# Sheet1.net
KiCad netlist of a schematic drawn in Altium Designer
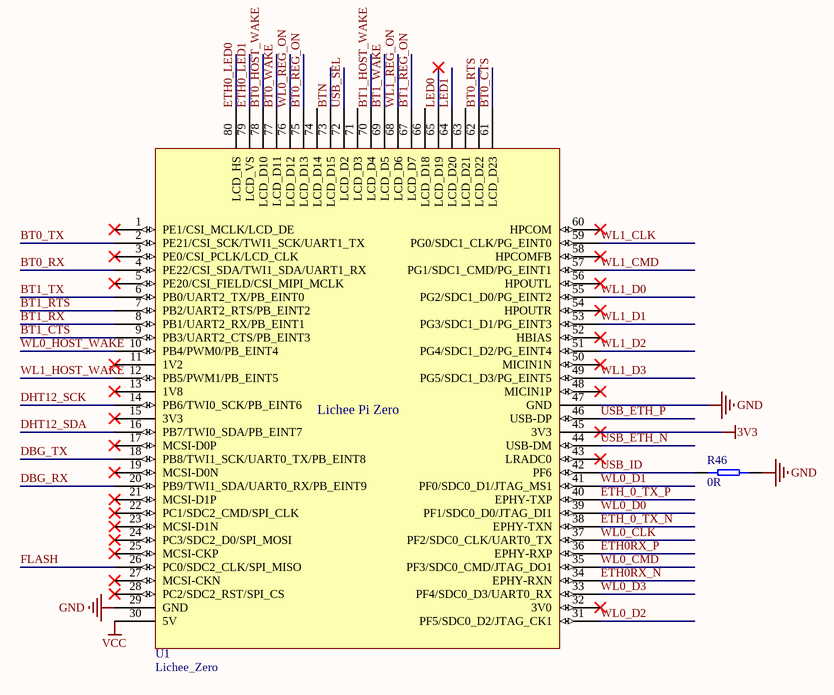
[diagram p0: Sheet1.SchDoc]

(export (version "E")
  (design (tool "Eeschema 10.0.6"))
  (components
    (comp (ref "R46") (value "0R") (footprint "0805R") (libsource (lib "Zero") (part "R")))
    (comp (ref "U1")
      (value "Lichee_Zero")
      (footprint "Lichee_Zero_Full")
      (description "Lichee_pizero LPZ1011")
      (libsource (lib "CTC") (part "Lichee_Zero_Full"))
    )
  )
  (nets
    (net (code "1") (name "/BT0_CTS") (class "Default")
      (node (ref "U1") (pin "61") (pinfunction "LCD_D23_61") (pintype "passive"))
    )
    (net (code "2") (name "/BT0_HOST_WAKE") (class "Default")
      (node (ref "U1") (pin "78") (pinfunction "LCD_D10_78") (pintype "passive"))
    )
    (net (code "3") (name "/BT0_REG_ON") (class "Default")
      (node (ref "U1") (pin "75") (pinfunction "LCD_D13_75") (pintype "passive"))
    )
    (net (code "4") (name "/BT0_RTS") (class "Default")
      (node (ref "U1") (pin "62") (pinfunction "LCD_D22_62") (pintype "passive"))
    )
    (net (code "5") (name "/BT0_RX") (class "Default")
      (node (ref "U1") (pin "4") (pinfunction "PE22/CSI_SDA/TWI1_SDA/UART1_RX_4") (pintype "bidirectional"))
    )
    (net (code "6") (name "/BT0_TX") (class "Default")
      (node (ref "U1") (pin "2") (pinfunction "PE21/CSI_SCK/TWI1_SCK/UART1_TX_2") (pintype "bidirectional"))
    )
    (net (code "7") (name "/BT0_WAKE") (class "Default")
      (node (ref "U1") (pin "77") (pinfunction "LCD_D11_77") (pintype "passive"))
    )
    (net (code "8") (name "/BT1_CTS") (class "Default")
      (node (ref "U1") (pin "9") (pinfunction "PB3/UART2_CTS/PB_EINT3_9") (pintype "bidirectional"))
    )
    (net (code "9") (name "/BT1_HOST_WAKE") (class "Default")
      (node (ref "U1") (pin "70") (pinfunction "LCD_D4_70") (pintype "passive"))
    )
    (net (code "10") (name "/BT1_REG_ON") (class "Default")
      (node (ref "U1") (pin "67") (pinfunction "LCD_D7_67") (pintype "passive"))
    )
    (net (code "11") (name "/BT1_RTS") (class "Default")
      (node (ref "U1") (pin "7") (pinfunction "PB2/UART2_RTS/PB_EINT2_7") (pintype "bidirectional"))
    )
    (net (code "12") (name "/BT1_RX") (class "Default")
      (node (ref "U1") (pin "8") (pinfunction "PB1/UART2_RX/PB_EINT1_8") (pintype "bidirectional"))
    )
    (net (code "13") (name "/BT1_TX") (class "Default")
      (node (ref "U1") (pin "6") (pinfunction "PB0/UART2_TX/PB_EINT0_6") (pintype "bidirectional"))
    )
    (net (code "14") (name "/BT1_WAKE") (class "Default")
      (node (ref "U1") (pin "69") (pinfunction "LCD_D5_69") (pintype "passive"))
    )
    (net (code "15") (name "/BTN") (class "Default")
      (node (ref "U1") (pin "73") (pinfunction "LCD_D15_73") (pintype "passive"))
    )
    (net (code "16") (name "/DBG_RX") (class "Default")
      (node (ref "U1") (pin "20") (pinfunction "PB9/TWI1_SDA/UART0_RX/PB_EINT9_20") (pintype "bidirectional"))
    )
    (net (code "17") (name "/DBG_TX") (class "Default")
      (node (ref "U1") (pin "18") (pinfunction "PB8/TWI1_SCK/UART0_TX/PB_EINT8_18") (pintype "bidirectional"))
    )
    (net (code "18") (name "/DHT12_SCK") (class "Default")
      (node (ref "U1") (pin "14") (pinfunction "PB6/TWI0_SCK/PB_EINT6_14") (pintype "bidirectional"))
    )
    (net (code "19") (name "/DHT12_SDA") (class "Default")
      (node (ref "U1") (pin "16") (pinfunction "PB7/TWI0_SDA/PB_EINT7_16") (pintype "bidirectional"))
    )
    (net (code "20") (name "/ETH0RX_N") (class "Default")
      (node (ref "U1") (pin "34") (pinfunction "EPHY-RXN_34") (pintype "bidirectional"))
    )
    (net (code "21") (name "/ETH0RX_P") (class "Default")
      (node (ref "U1") (pin "36") (pinfunction "EPHY-RXP_36") (pintype "bidirectional"))
    )
    (net (code "22") (name "/ETH0_LED0") (class "Default")
      (node (ref "U1") (pin "80") (pinfunction "LCD_HS_80") (pintype "passive"))
    )
    (net (code "23") (name "/ETH0_LED1") (class "Default")
      (node (ref "U1") (pin "79") (pinfunction "LCD_VS_79") (pintype "passive"))
    )
    (net (code "24") (name "/ETH_0_TX_N") (class "Default")
      (node (ref "U1") (pin "38") (pinfunction "EPHY-TXN_38") (pintype "bidirectional"))
    )
    (net (code "25") (name "/ETH_0_TX_P") (class "Default")
      (node (ref "U1") (pin "40") (pinfunction "EPHY-TXP_40") (pintype "bidirectional"))
    )
    (net (code "26") (name "/FLASH") (class "Default")
      (node (ref "U1") (pin "26") (pinfunction "PC0/SDC2_CLK/SPI_MISO_26") (pintype "bidirectional"))
    )
    (net (code "27") (name "/LED0") (class "Default")
      (node (ref "U1") (pin "65") (pinfunction "LCD_D19_65") (pintype "passive+no_connect"))
    )
    (net (code "28") (name "/LED1") (class "Default")
      (node (ref "U1") (pin "64") (pinfunction "LCD_D20_64") (pintype "passive"))
    )
    (net (code "29") (name "/USB_ETH_N") (class "Default")
      (node (ref "U1") (pin "44") (pinfunction "USB-DM_44") (pintype "bidirectional"))
    )
    (net (code "30") (name "/USB_ETH_P") (class "Default")
      (node (ref "U1") (pin "46") (pinfunction "USB-DP_46") (pintype "bidirectional"))
    )
    (net (code "31") (name "/USB_ID") (class "Default")
      (node (ref "R46") (pin "1") (pinfunction "1_1") (pintype "passive"))
      (node (ref "U1") (pin "42") (pinfunction "PF6_42") (pintype "bidirectional"))
    )
    (net (code "32") (name "/USB_SEL") (class "Default")
      (node (ref "U1") (pin "72") (pinfunction "LCD_D2_72") (pintype "passive"))
    )
    (net (code "33") (name "/WL0_CLK") (class "Default")
      (node (ref "U1") (pin "37") (pinfunction "PF2/SDC0_CLK/UART0_TX_37") (pintype "bidirectional"))
    )
    (net (code "34") (name "/WL0_CMD") (class "Default")
      (node (ref "U1") (pin "35") (pinfunction "PF3/SDC0_CMD/JTAG_DO1_35") (pintype "bidirectional"))
    )
    (net (code "35") (name "/WL0_D0") (class "Default")
      (node (ref "U1") (pin "39") (pinfunction "PF1/SDC0_D0/JTAG_DI1_39") (pintype "bidirectional"))
    )
    (net (code "36") (name "/WL0_D1") (class "Default")
      (node (ref "U1") (pin "41") (pinfunction "PF0/SDC0_D1/JTAG_MS1_41") (pintype "bidirectional"))
    )
    (net (code "37") (name "/WL0_D2") (class "Default")
      (node (ref "U1") (pin "31") (pinfunction "PF5/SDC0_D2/JTAG_CK1_31") (pintype "bidirectional"))
    )
    (net (code "38") (name "/WL0_D3") (class "Default")
      (node (ref "U1") (pin "33") (pinfunction "PF4/SDC0_D3/UART0_RX_33") (pintype "bidirectional"))
    )
    (net (code "39") (name "/WL0_HOST_WAKE") (class "Default")
      (node (ref "U1") (pin "10") (pinfunction "PB4/PWM0/PB_EINT4_10") (pintype "bidirectional"))
    )
    (net (code "40") (name "/WL0_REG_ON") (class "Default")
      (node (ref "U1") (pin "76") (pinfunction "LCD_D12_76") (pintype "passive"))
    )
    (net (code "41") (name "/WL1_CLK") (class "Default")
      (node (ref "U1") (pin "59") (pinfunction "PG0/SDC1_CLK/PG_EINT0_59") (pintype "bidirectional"))
    )
    (net (code "42") (name "/WL1_CMD") (class "Default")
      (node (ref "U1") (pin "57") (pinfunction "PG1/SDC1_CMD/PG_EINT1_57") (pintype "bidirectional"))
    )
    (net (code "43") (name "/WL1_D0") (class "Default")
      (node (ref "U1") (pin "55") (pinfunction "PG2/SDC1_D0/PG_EINT2_55") (pintype "bidirectional"))
    )
    (net (code "44") (name "/WL1_D1") (class "Default")
      (node (ref "U1") (pin "53") (pinfunction "PG3/SDC1_D1/PG_EINT3_53") (pintype "bidirectional"))
    )
    (net (code "45") (name "/WL1_D2") (class "Default")
      (node (ref "U1") (pin "51") (pinfunction "PG4/SDC1_D2/PG_EINT4_51") (pintype "bidirectional"))
    )
    (net (code "46") (name "/WL1_D3") (class "Default")
      (node (ref "U1") (pin "49") (pinfunction "PG5/SDC1_D3/PG_EINT5_49") (pintype "bidirectional"))
    )
    (net (code "47") (name "/WL1_HOST_WAKE") (class "Default")
      (node (ref "U1") (pin "12") (pinfunction "PB5/PWM1/PB_EINT5_12") (pintype "bidirectional"))
    )
    (net (code "48") (name "/WL1_REG_ON") (class "Default")
      (node (ref "U1") (pin "68") (pinfunction "LCD_D6_68") (pintype "passive"))
    )
    (net (code "49") (name "3V3") (class "Default")
      (node (ref "U1") (pin "45") (pinfunction "3V3_45") (pintype "power_in"))
    )
    (net (code "50") (name "GND") (class "Default")
      (node (ref "R46") (pin "2") (pinfunction "2_2") (pintype "passive"))
      (node (ref "U1") (pin "29") (pinfunction "GND_29") (pintype "power_in"))
      (node (ref "U1") (pin "47") (pinfunction "GND_47") (pintype "power_in"))
    )
    (net (code "51") (name "VCC") (class "Default")
      (node (ref "U1") (pin "30") (pinfunction "5V_30") (pintype "power_in"))
    )
    (net (code "52") (name "unconnected-(U1-1V2-Pad11)") (class "Default")
      (node (ref "U1") (pin "11") (pinfunction "1V2_11") (pintype "power_in+no_connect"))
    )
    (net (code "53") (name "unconnected-(U1-1V8-Pad13)") (class "Default")
      (node (ref "U1") (pin "13") (pinfunction "1V8_13") (pintype "power_in+no_connect"))
    )
    (net (code "54") (name "unconnected-(U1-3V0-Pad32)") (class "Default")
      (node (ref "U1") (pin "32") (pinfunction "3V0_32") (pintype "bidirectional+no_connect"))
    )
    (net (code "55") (name "unconnected-(U1-3V3-Pad15)") (class "Default")
      (node (ref "U1") (pin "15") (pinfunction "3V3_15") (pintype "power_in+no_connect"))
    )
    (net (code "56") (name "unconnected-(U1-HBIAS-Pad52)") (class "Default")
      (node (ref "U1") (pin "52") (pinfunction "HBIAS_52") (pintype "bidirectional+no_connect"))
    )
    (net (code "57") (name "unconnected-(U1-HPCOM-Pad60)") (class "Default")
      (node (ref "U1") (pin "60") (pinfunction "HPCOM_60") (pintype "bidirectional+no_connect"))
    )
    (net (code "58") (name "unconnected-(U1-HPCOMFB-Pad58)") (class "Default")
      (node (ref "U1") (pin "58") (pinfunction "HPCOMFB_58") (pintype "bidirectional+no_connect"))
    )
    (net (code "59") (name "unconnected-(U1-HPOUTL-Pad56)") (class "Default")
      (node (ref "U1") (pin "56") (pinfunction "HPOUTL_56") (pintype "bidirectional+no_connect"))
    )
    (net (code "60") (name "unconnected-(U1-HPOUTR-Pad54)") (class "Default")
      (node (ref "U1") (pin "54") (pinfunction "HPOUTR_54") (pintype "bidirectional+no_connect"))
    )
    (net (code "61") (name "unconnected-(U1-LCD_D3-Pad71)") (class "Default")
      (node (ref "U1") (pin "71") (pinfunction "LCD_D3_71") (pintype "passive"))
    )
    (net (code "62") (name "unconnected-(U1-LCD_D14-Pad74)") (class "Default")
      (node (ref "U1") (pin "74") (pinfunction "LCD_D14_74") (pintype "passive"))
    )
    (net (code "63") (name "unconnected-(U1-LCD_D18-Pad66)") (class "Default")
      (node (ref "U1") (pin "66") (pinfunction "LCD_D18_66") (pintype "passive"))
    )
    (net (code "64") (name "unconnected-(U1-LCD_D21-Pad63)") (class "Default")
      (node (ref "U1") (pin "63") (pinfunction "LCD_D21_63") (pintype "passive"))
    )
    (net (code "65") (name "unconnected-(U1-LRADC0-Pad43)") (class "Default")
      (node (ref "U1") (pin "43") (pinfunction "LRADC0_43") (pintype "bidirectional+no_connect"))
    )
    (net (code "66") (name "unconnected-(U1-MCSI-CKN-Pad27)") (class "Default")
      (node (ref "U1") (pin "27") (pinfunction "MCSI-CKN_27") (pintype "bidirectional+no_connect"))
    )
    (net (code "67") (name "unconnected-(U1-MCSI-CKP-Pad25)") (class "Default")
      (node (ref "U1") (pin "25") (pinfunction "MCSI-CKP_25") (pintype "bidirectional+no_connect"))
    )
    (net (code "68") (name "unconnected-(U1-MCSI-D0N-Pad19)") (class "Default")
      (node (ref "U1") (pin "19") (pinfunction "MCSI-D0N_19") (pintype "bidirectional+no_connect"))
    )
    (net (code "69") (name "unconnected-(U1-MCSI-D0P-Pad17)") (class "Default")
      (node (ref "U1") (pin "17") (pinfunction "MCSI-D0P_17") (pintype "bidirectional+no_connect"))
    )
    (net (code "70") (name "unconnected-(U1-MCSI-D1N-Pad23)") (class "Default")
      (node (ref "U1") (pin "23") (pinfunction "MCSI-D1N_23") (pintype "bidirectional+no_connect"))
    )
    (net (code "71") (name "unconnected-(U1-MCSI-D1P-Pad21)") (class "Default")
      (node (ref "U1") (pin "21") (pinfunction "MCSI-D1P_21") (pintype "bidirectional+no_connect"))
    )
    (net (code "72") (name "unconnected-(U1-MICIN1N-Pad50)") (class "Default")
      (node (ref "U1") (pin "50") (pinfunction "MICIN1N_50") (pintype "bidirectional+no_connect"))
    )
    (net (code "73") (name "unconnected-(U1-MICIN1P-Pad48)") (class "Default")
      (node (ref "U1") (pin "48") (pinfunction "MICIN1P_48") (pintype "bidirectional+no_connect"))
    )
    (net (code "74") (name "unconnected-(U1-PC1{slash}SDC2_CMD{slash}SPI_CLK-Pad22)") (class "Default")
      (node (ref "U1") (pin "22") (pinfunction "PC1/SDC2_CMD/SPI_CLK_22") (pintype "bidirectional+no_connect"))
    )
    (net (code "75") (name "unconnected-(U1-PC2{slash}SDC2_RST{slash}SPI_CS-Pad28)") (class "Default")
      (node (ref "U1") (pin "28") (pinfunction "PC2/SDC2_RST/SPI_CS_28") (pintype "bidirectional+no_connect"))
    )
    (net (code "76") (name "unconnected-(U1-PC3{slash}SDC2_D0{slash}SPI_MOSI-Pad24)") (class "Default")
      (node (ref "U1") (pin "24") (pinfunction "PC3/SDC2_D0/SPI_MOSI_24") (pintype "bidirectional+no_connect"))
    )
    (net (code "77") (name "unconnected-(U1-PE0{slash}CSI_PCLK{slash}LCD_CLK-Pad3)") (class "Default")
      (node (ref "U1") (pin "3") (pinfunction "PE0/CSI_PCLK/LCD_CLK_3") (pintype "bidirectional+no_connect"))
    )
    (net (code "78") (name "unconnected-(U1-PE1{slash}CSI_MCLK{slash}LCD_DE-Pad1)") (class "Default")
      (node (ref "U1") (pin "1") (pinfunction "PE1/CSI_MCLK/LCD_DE_1") (pintype "bidirectional+no_connect"))
    )
    (net (code "79") (name "unconnected-(U1-PE20{slash}CSI_FIELD{slash}CSI_MIPI_MCLK-Pad5)") (class "Default")
      (node (ref "U1") (pin "5") (pinfunction "PE20/CSI_FIELD/CSI_MIPI_MCLK_5") (pintype "bidirectional+no_connect"))
    )
  )
)
